# v1.net
KiCad netlist of a schematic drawn in EAGLE
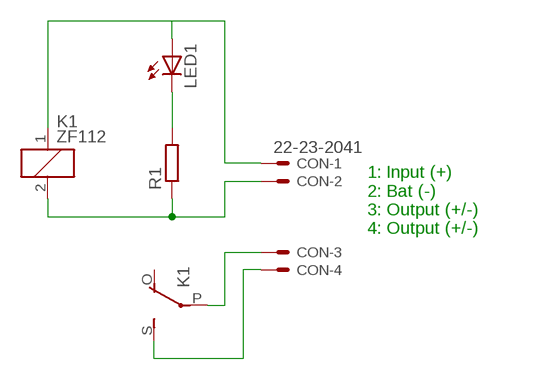
[diagram p0: schematic, sheet 1]

(export (version "E")
  (design (tool "Eeschema 10.0.6"))
  (components
    (comp (ref "CON")
      (value "22-23-2041")
      (footprint "eagle-import:22-23-2041")
      (fields (field (name "MF") "MOLEX"))
      (libsource (lib "eagle-import") (part "22-23-2041"))
    )
    (comp (ref "K1")
      (value "ZF112")
      (footprint "eagle-import:ZF112")
      (libsource (lib "eagle-import") (part "ZF112"))
    )
    (comp (ref "LED1")
      (value "LED3MM")
      (footprint "eagle-import:LED3MM")
      (libsource (lib "eagle-import") (part "LED3MM"))
    )
    (comp (ref "R1")
      (value "R-EU_0207/12")
      (footprint "eagle-import:0207_12")
      (libsource (lib "eagle-import") (part "R-EU_0207/12"))
    )
  )
  (nets
    (net (code "1") (name "Net-(CONA-S)") (class "Default")
      (node (ref "CON") (pin "1") (pinfunction "S_1") (pintype "passive"))
      (node (ref "K1") (pin "1") (pinfunction "1_1") (pintype "passive"))
      (node (ref "LED1") (pin "A") (pinfunction "A_A") (pintype "passive"))
    )
    (net (code "2") (name "Net-(CONB-S)") (class "Default")
      (node (ref "CON") (pin "2") (pinfunction "S_2") (pintype "passive"))
      (node (ref "K1") (pin "2") (pinfunction "2_2") (pintype "passive"))
      (node (ref "R1") (pin "1") (pinfunction "1_1") (pintype "passive"))
    )
    (net (code "3") (name "Net-(CONC-S)") (class "Default")
      (node (ref "CON") (pin "3") (pinfunction "S_3") (pintype "passive"))
      (node (ref "K1") (pin "P") (pinfunction "P_P") (pintype "passive"))
    )
    (net (code "4") (name "Net-(COND-S)") (class "Default")
      (node (ref "CON") (pin "4") (pinfunction "S_4") (pintype "passive"))
      (node (ref "K1") (pin "S") (pinfunction "S_S") (pintype "passive"))
    )
    (net (code "5") (name "Net-(LED1-C)") (class "Default")
      (node (ref "LED1") (pin "K") (pinfunction "C_K") (pintype "passive"))
      (node (ref "R1") (pin "2") (pinfunction "2_2") (pintype "passive"))
    )
    (net (code "6") (name "unconnected-(K1-PadO)") (class "Default")
      (node (ref "K1") (pin "O") (pinfunction "O_O") (pintype "passive"))
    )
  )
)
